# gameoflife.net
KiCad netlist of a schematic drawn in EAGLE
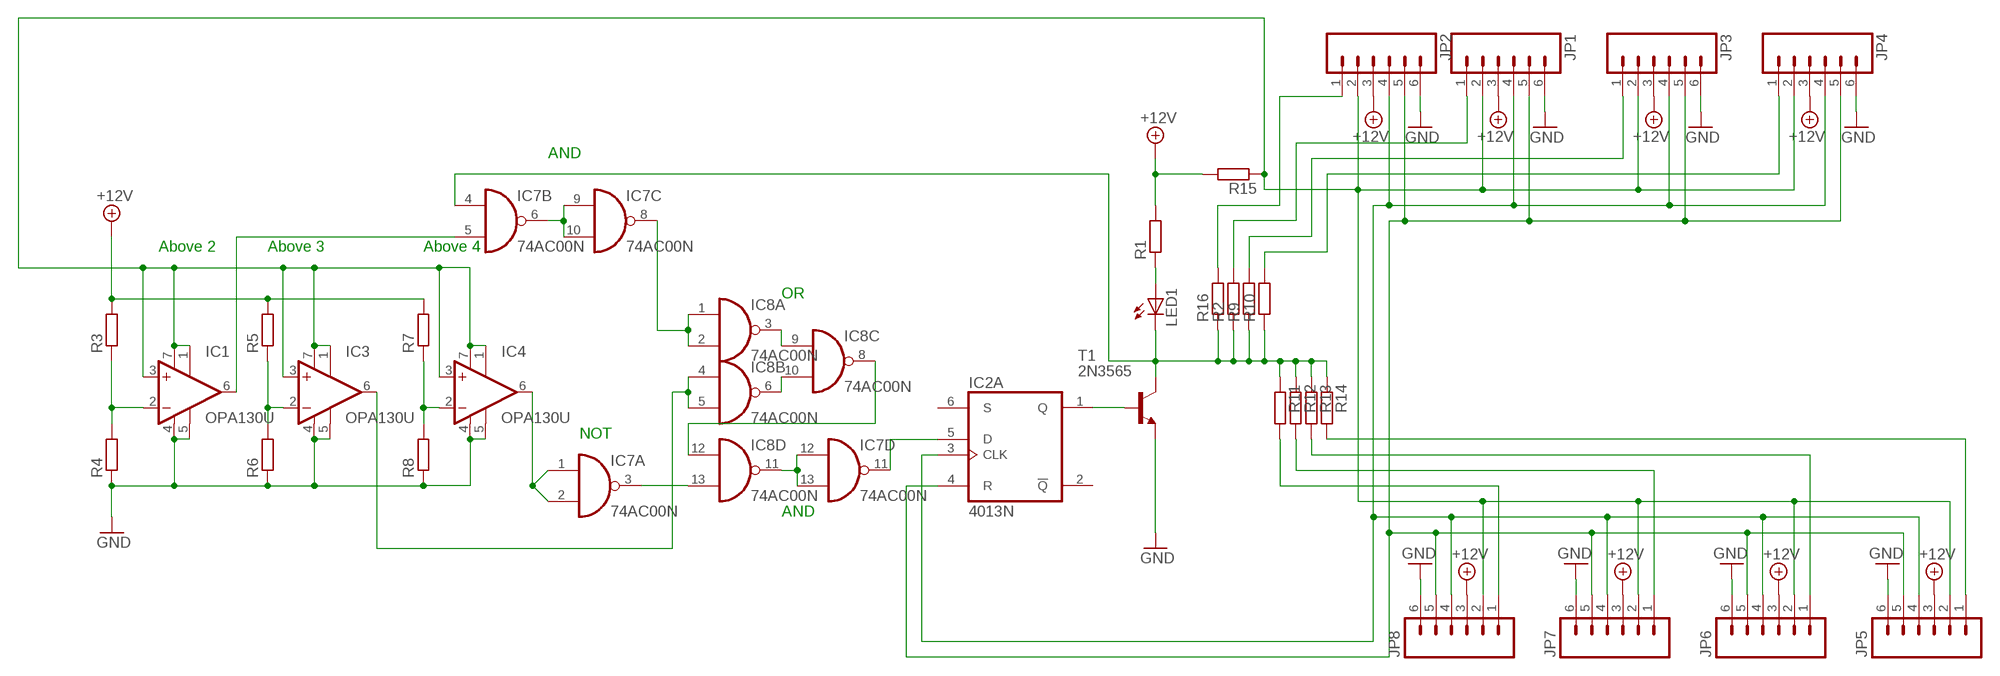
[diagram p0: schematic, sheet 1]

(export (version "E")
  (design (tool "Eeschema 10.0.6"))
  (components
    (comp (ref "IC1")
      (value "OPA130U")
      (footprint "eagle-import:SO08")
      (fields (field (name "MF") "TEXAS INSTRUMENTS") (field (name "MPN") "OPA130UA"))
      (libsource (lib "eagle-import") (part "OPA130U"))
    )
    (comp (ref "IC2")
      (value "4013N")
      (footprint "eagle-import:DIL14")
      (libsource (lib "eagle-import") (part "4013N"))
    )
    (comp (ref "IC3")
      (value "OPA130U")
      (footprint "eagle-import:SO08")
      (fields (field (name "MF") "TEXAS INSTRUMENTS") (field (name "MPN") "OPA130UA"))
      (libsource (lib "eagle-import") (part "OPA130U"))
    )
    (comp (ref "IC4")
      (value "OPA130U")
      (footprint "eagle-import:SO08")
      (fields (field (name "MF") "TEXAS INSTRUMENTS") (field (name "MPN") "OPA130UA"))
      (libsource (lib "eagle-import") (part "OPA130U"))
    )
    (comp (ref "IC7")
      (value "74AC00N")
      (footprint "eagle-import:DIL14")
      (libsource (lib "eagle-import") (part "7400NAC"))
    )
    (comp (ref "IC8")
      (value "74AC00N")
      (footprint "eagle-import:DIL14")
      (libsource (lib "eagle-import") (part "7400NAC"))
    )
    (comp (ref "JP1")
      (value "M06SILK_FEMALE_PTH")
      (footprint "eagle-import:1X06")
      (libsource (lib "eagle-import") (part "M06SILK_FEMALE_PTH"))
    )
    (comp (ref "JP2")
      (value "M06SILK_FEMALE_PTH")
      (footprint "eagle-import:1X06")
      (libsource (lib "eagle-import") (part "M06SILK_FEMALE_PTH"))
    )
    (comp (ref "JP3")
      (value "M06SILK_FEMALE_PTH")
      (footprint "eagle-import:1X06")
      (libsource (lib "eagle-import") (part "M06SILK_FEMALE_PTH"))
    )
    (comp (ref "JP4")
      (value "M06SILK_FEMALE_PTH")
      (footprint "eagle-import:1X06")
      (libsource (lib "eagle-import") (part "M06SILK_FEMALE_PTH"))
    )
    (comp (ref "JP5")
      (value "M06SILK_FEMALE_PTH")
      (footprint "eagle-import:1X06")
      (libsource (lib "eagle-import") (part "M06SILK_FEMALE_PTH"))
    )
    (comp (ref "JP6")
      (value "M06SILK_FEMALE_PTH")
      (footprint "eagle-import:1X06")
      (libsource (lib "eagle-import") (part "M06SILK_FEMALE_PTH"))
    )
    (comp (ref "JP7")
      (value "M06SILK_FEMALE_PTH")
      (footprint "eagle-import:1X06")
      (libsource (lib "eagle-import") (part "M06SILK_FEMALE_PTH"))
    )
    (comp (ref "JP8")
      (value "M06SILK_FEMALE_PTH")
      (footprint "eagle-import:1X06")
      (libsource (lib "eagle-import") (part "M06SILK_FEMALE_PTH"))
    )
    (comp (ref "LED1")
      (value "LED3MM")
      (footprint "eagle-import:LED3MM")
      (libsource (lib "eagle-import") (part "LED3MM"))
    )
    (comp (ref "R1")
      (value "R-EU_0207/10")
      (footprint "eagle-import:0207_10")
      (libsource (lib "eagle-import") (part "R-EU_0207/10"))
    )
    (comp (ref "R2")
      (value "R-EU_0207/10")
      (footprint "eagle-import:0207_10")
      (libsource (lib "eagle-import") (part "R-EU_0207/10"))
    )
    (comp (ref "R3")
      (value "R-EU_0207/10")
      (footprint "eagle-import:0207_10")
      (libsource (lib "eagle-import") (part "R-EU_0207/10"))
    )
    (comp (ref "R4")
      (value "R-EU_0207/10")
      (footprint "eagle-import:0207_10")
      (libsource (lib "eagle-import") (part "R-EU_0207/10"))
    )
    (comp (ref "R5")
      (value "R-EU_0207/10")
      (footprint "eagle-import:0207_10")
      (libsource (lib "eagle-import") (part "R-EU_0207/10"))
    )
    (comp (ref "R6")
      (value "R-EU_0207/10")
      (footprint "eagle-import:0207_10")
      (libsource (lib "eagle-import") (part "R-EU_0207/10"))
    )
    (comp (ref "R7")
      (value "R-EU_0207/10")
      (footprint "eagle-import:0207_10")
      (libsource (lib "eagle-import") (part "R-EU_0207/10"))
    )
    (comp (ref "R8")
      (value "R-EU_0207/10")
      (footprint "eagle-import:0207_10")
      (libsource (lib "eagle-import") (part "R-EU_0207/10"))
    )
    (comp (ref "R9")
      (value "R-EU_0207/10")
      (footprint "eagle-import:0207_10")
      (libsource (lib "eagle-import") (part "R-EU_0207/10"))
    )
    (comp (ref "R10")
      (value "R-EU_0207/10")
      (footprint "eagle-import:0207_10")
      (libsource (lib "eagle-import") (part "R-EU_0207/10"))
    )
    (comp (ref "R11")
      (value "R-EU_0207/10")
      (footprint "eagle-import:0207_10")
      (libsource (lib "eagle-import") (part "R-EU_0207/10"))
    )
    (comp (ref "R12")
      (value "R-EU_0207/10")
      (footprint "eagle-import:0207_10")
      (libsource (lib "eagle-import") (part "R-EU_0207/10"))
    )
    (comp (ref "R13")
      (value "R-EU_0207/10")
      (footprint "eagle-import:0207_10")
      (libsource (lib "eagle-import") (part "R-EU_0207/10"))
    )
    (comp (ref "R14")
      (value "R-EU_0207/10")
      (footprint "eagle-import:0207_10")
      (libsource (lib "eagle-import") (part "R-EU_0207/10"))
    )
    (comp (ref "R15")
      (value "R-EU_0207/10")
      (footprint "eagle-import:0207_10")
      (libsource (lib "eagle-import") (part "R-EU_0207/10"))
    )
    (comp (ref "R16")
      (value "R-EU_0207/10")
      (footprint "eagle-import:0207_10")
      (libsource (lib "eagle-import") (part "R-EU_0207/10"))
    )
    (comp (ref "T1")
      (value "2N3565")
      (footprint "eagle-import:TO92")
      (libsource (lib "eagle-import") (part "2N3565"))
    )
  )
  (nets
    (net (code "1") (name "+12V") (class "Default")
      (node (ref "JP1") (pin "3") (pinfunction "3_3") (pintype "passive"))
      (node (ref "JP2") (pin "3") (pinfunction "3_3") (pintype "passive"))
      (node (ref "JP3") (pin "3") (pinfunction "3_3") (pintype "passive"))
      (node (ref "JP4") (pin "3") (pinfunction "3_3") (pintype "passive"))
      (node (ref "JP5") (pin "3") (pinfunction "3_3") (pintype "passive"))
      (node (ref "JP6") (pin "3") (pinfunction "3_3") (pintype "passive"))
      (node (ref "JP7") (pin "3") (pinfunction "3_3") (pintype "passive"))
      (node (ref "JP8") (pin "3") (pinfunction "3_3") (pintype "passive"))
      (node (ref "R1") (pin "2") (pinfunction "2_2") (pintype "passive"))
      (node (ref "R15") (pin "2") (pinfunction "2_2") (pintype "passive"))
      (node (ref "R3") (pin "2") (pinfunction "2_2") (pintype "passive"))
      (node (ref "R5") (pin "2") (pinfunction "2_2") (pintype "passive"))
      (node (ref "R7") (pin "2") (pinfunction "2_2") (pintype "passive"))
    )
    (net (code "2") (name "GND") (class "Default")
      (node (ref "IC1") (pin "4") (pinfunction "V-_4") (pintype "power_in"))
      (node (ref "IC1") (pin "5") (pinfunction "TRIM2_5") (pintype "passive"))
      (node (ref "IC3") (pin "4") (pinfunction "V-_4") (pintype "power_in"))
      (node (ref "IC3") (pin "5") (pinfunction "TRIM2_5") (pintype "passive"))
      (node (ref "IC4") (pin "4") (pinfunction "V-_4") (pintype "power_in"))
      (node (ref "IC4") (pin "5") (pinfunction "TRIM2_5") (pintype "passive"))
      (node (ref "JP1") (pin "6") (pinfunction "6_6") (pintype "passive"))
      (node (ref "JP2") (pin "6") (pinfunction "6_6") (pintype "passive"))
      (node (ref "JP3") (pin "6") (pinfunction "6_6") (pintype "passive"))
      (node (ref "JP4") (pin "6") (pinfunction "6_6") (pintype "passive"))
      (node (ref "JP5") (pin "6") (pinfunction "6_6") (pintype "passive"))
      (node (ref "JP6") (pin "6") (pinfunction "6_6") (pintype "passive"))
      (node (ref "JP7") (pin "6") (pinfunction "6_6") (pintype "passive"))
      (node (ref "JP8") (pin "6") (pinfunction "6_6") (pintype "passive"))
      (node (ref "R4") (pin "1") (pinfunction "1_1") (pintype "passive"))
      (node (ref "R6") (pin "1") (pinfunction "1_1") (pintype "passive"))
      (node (ref "R8") (pin "1") (pinfunction "1_1") (pintype "passive"))
      (node (ref "T1") (pin "3") (pinfunction "E_3") (pintype "passive"))
    )
    (net (code "3") (name "Net-(IC1-+IN)") (class "Default")
      (node (ref "IC1") (pin "1") (pinfunction "TRIM1_1") (pintype "passive"))
      (node (ref "IC1") (pin "3") (pinfunction "+IN_3") (pintype "input"))
      (node (ref "IC1") (pin "7") (pinfunction "V+_7") (pintype "power_in"))
      (node (ref "IC3") (pin "1") (pinfunction "TRIM1_1") (pintype "passive"))
      (node (ref "IC3") (pin "3") (pinfunction "+IN_3") (pintype "input"))
      (node (ref "IC3") (pin "7") (pinfunction "V+_7") (pintype "power_in"))
      (node (ref "IC4") (pin "1") (pinfunction "TRIM1_1") (pintype "passive"))
      (node (ref "IC4") (pin "3") (pinfunction "+IN_3") (pintype "input"))
      (node (ref "IC4") (pin "7") (pinfunction "V+_7") (pintype "power_in"))
      (node (ref "JP1") (pin "2") (pinfunction "2_2") (pintype "passive"))
      (node (ref "JP2") (pin "2") (pinfunction "2_2") (pintype "passive"))
      (node (ref "JP3") (pin "2") (pinfunction "2_2") (pintype "passive"))
      (node (ref "JP4") (pin "2") (pinfunction "2_2") (pintype "passive"))
      (node (ref "JP5") (pin "2") (pinfunction "2_2") (pintype "passive"))
      (node (ref "JP6") (pin "2") (pinfunction "2_2") (pintype "passive"))
      (node (ref "JP7") (pin "2") (pinfunction "2_2") (pintype "passive"))
      (node (ref "JP8") (pin "2") (pinfunction "2_2") (pintype "passive"))
      (node (ref "R15") (pin "1") (pinfunction "1_1") (pintype "passive"))
    )
    (net (code "4") (name "Net-(IC1--IN)") (class "Default")
      (node (ref "IC1") (pin "2") (pinfunction "-IN_2") (pintype "input"))
      (node (ref "R3") (pin "1") (pinfunction "1_1") (pintype "passive"))
      (node (ref "R4") (pin "2") (pinfunction "2_2") (pintype "passive"))
    )
    (net (code "5") (name "Net-(IC1-OUT)") (class "Default")
      (node (ref "IC1") (pin "6") (pinfunction "OUT_6") (pintype "output"))
      (node (ref "IC7") (pin "5") (pinfunction "I1_5") (pintype "input"))
    )
    (net (code "6") (name "Net-(IC2A-CLK)") (class "Default")
      (node (ref "IC2") (pin "3") (pinfunction "CLK_3") (pintype "input"))
      (node (ref "JP1") (pin "4") (pinfunction "4_4") (pintype "passive"))
      (node (ref "JP2") (pin "4") (pinfunction "4_4") (pintype "passive"))
      (node (ref "JP3") (pin "4") (pinfunction "4_4") (pintype "passive"))
      (node (ref "JP4") (pin "4") (pinfunction "4_4") (pintype "passive"))
      (node (ref "JP5") (pin "4") (pinfunction "4_4") (pintype "passive"))
      (node (ref "JP6") (pin "4") (pinfunction "4_4") (pintype "passive"))
      (node (ref "JP7") (pin "4") (pinfunction "4_4") (pintype "passive"))
      (node (ref "JP8") (pin "4") (pinfunction "4_4") (pintype "passive"))
    )
    (net (code "7") (name "Net-(IC2A-D)") (class "Default")
      (node (ref "IC2") (pin "5") (pinfunction "D_5") (pintype "input"))
      (node (ref "IC7") (pin "11") (pinfunction "O_11") (pintype "output"))
    )
    (net (code "8") (name "Net-(IC2A-Q)") (class "Default")
      (node (ref "IC2") (pin "1") (pinfunction "Q_1") (pintype "output"))
      (node (ref "T1") (pin "2") (pinfunction "B_2") (pintype "passive"))
    )
    (net (code "9") (name "Net-(IC2A-R)") (class "Default")
      (node (ref "IC2") (pin "4") (pinfunction "R_4") (pintype "input"))
      (node (ref "JP1") (pin "5") (pinfunction "5_5") (pintype "passive"))
      (node (ref "JP2") (pin "5") (pinfunction "5_5") (pintype "passive"))
      (node (ref "JP3") (pin "5") (pinfunction "5_5") (pintype "passive"))
      (node (ref "JP4") (pin "5") (pinfunction "5_5") (pintype "passive"))
      (node (ref "JP5") (pin "5") (pinfunction "5_5") (pintype "passive"))
      (node (ref "JP6") (pin "5") (pinfunction "5_5") (pintype "passive"))
      (node (ref "JP7") (pin "5") (pinfunction "5_5") (pintype "passive"))
      (node (ref "JP8") (pin "5") (pinfunction "5_5") (pintype "passive"))
    )
    (net (code "10") (name "Net-(IC3--IN)") (class "Default")
      (node (ref "IC3") (pin "2") (pinfunction "-IN_2") (pintype "input"))
      (node (ref "R5") (pin "1") (pinfunction "1_1") (pintype "passive"))
      (node (ref "R6") (pin "2") (pinfunction "2_2") (pintype "passive"))
    )
    (net (code "11") (name "Net-(IC3-OUT)") (class "Default")
      (node (ref "IC3") (pin "6") (pinfunction "OUT_6") (pintype "output"))
      (node (ref "IC8") (pin "4") (pinfunction "I0_4") (pintype "input"))
      (node (ref "IC8") (pin "5") (pinfunction "I1_5") (pintype "input"))
    )
    (net (code "12") (name "Net-(IC4--IN)") (class "Default")
      (node (ref "IC4") (pin "2") (pinfunction "-IN_2") (pintype "input"))
      (node (ref "R7") (pin "1") (pinfunction "1_1") (pintype "passive"))
      (node (ref "R8") (pin "2") (pinfunction "2_2") (pintype "passive"))
    )
    (net (code "13") (name "Net-(IC4-OUT)") (class "Default")
      (node (ref "IC4") (pin "6") (pinfunction "OUT_6") (pintype "output"))
      (node (ref "IC7") (pin "1") (pinfunction "I0_1") (pintype "input"))
      (node (ref "IC7") (pin "2") (pinfunction "I1_2") (pintype "input"))
    )
    (net (code "14") (name "Net-(IC7A-O)") (class "Default")
      (node (ref "IC7") (pin "3") (pinfunction "O_3") (pintype "output"))
      (node (ref "IC8") (pin "13") (pinfunction "I1_13") (pintype "input"))
    )
    (net (code "15") (name "Net-(IC7B-I0)") (class "Default")
      (node (ref "IC7") (pin "4") (pinfunction "I0_4") (pintype "input"))
      (node (ref "LED1") (pin "K") (pinfunction "C_K") (pintype "passive"))
      (node (ref "R10") (pin "1") (pinfunction "1_1") (pintype "passive"))
      (node (ref "R11") (pin "1") (pinfunction "1_1") (pintype "passive"))
      (node (ref "R12") (pin "1") (pinfunction "1_1") (pintype "passive"))
      (node (ref "R13") (pin "1") (pinfunction "1_1") (pintype "passive"))
      (node (ref "R14") (pin "1") (pinfunction "1_1") (pintype "passive"))
      (node (ref "R16") (pin "1") (pinfunction "1_1") (pintype "passive"))
      (node (ref "R2") (pin "1") (pinfunction "1_1") (pintype "passive"))
      (node (ref "R9") (pin "1") (pinfunction "1_1") (pintype "passive"))
      (node (ref "T1") (pin "1") (pinfunction "C_1") (pintype "passive"))
    )
    (net (code "16") (name "Net-(IC7B-O)") (class "Default")
      (node (ref "IC7") (pin "10") (pinfunction "I1_10") (pintype "input"))
      (node (ref "IC7") (pin "6") (pinfunction "O_6") (pintype "output"))
      (node (ref "IC7") (pin "9") (pinfunction "I0_9") (pintype "input"))
    )
    (net (code "17") (name "Net-(IC7C-O)") (class "Default")
      (node (ref "IC7") (pin "8") (pinfunction "O_8") (pintype "output"))
      (node (ref "IC8") (pin "1") (pinfunction "I0_1") (pintype "input"))
      (node (ref "IC8") (pin "2") (pinfunction "I1_2") (pintype "input"))
    )
    (net (code "18") (name "Net-(IC7D-I0)") (class "Default")
      (node (ref "IC7") (pin "12") (pinfunction "I0_12") (pintype "input"))
      (node (ref "IC7") (pin "13") (pinfunction "I1_13") (pintype "input"))
      (node (ref "IC8") (pin "11") (pinfunction "O_11") (pintype "output"))
    )
    (net (code "19") (name "Net-(IC8A-O)") (class "Default")
      (node (ref "IC8") (pin "3") (pinfunction "O_3") (pintype "output"))
      (node (ref "IC8") (pin "9") (pinfunction "I0_9") (pintype "input"))
    )
    (net (code "20") (name "Net-(IC8B-O)") (class "Default")
      (node (ref "IC8") (pin "10") (pinfunction "I1_10") (pintype "input"))
      (node (ref "IC8") (pin "6") (pinfunction "O_6") (pintype "output"))
    )
    (net (code "21") (name "Net-(IC8C-O)") (class "Default")
      (node (ref "IC8") (pin "12") (pinfunction "I0_12") (pintype "input"))
      (node (ref "IC8") (pin "8") (pinfunction "O_8") (pintype "output"))
    )
    (net (code "22") (name "Net-(JP1-Pad1)") (class "Default")
      (node (ref "JP1") (pin "1") (pinfunction "1_1") (pintype "passive"))
      (node (ref "R2") (pin "2") (pinfunction "2_2") (pintype "passive"))
    )
    (net (code "23") (name "Net-(JP2-Pad1)") (class "Default")
      (node (ref "JP2") (pin "1") (pinfunction "1_1") (pintype "passive"))
      (node (ref "R16") (pin "2") (pinfunction "2_2") (pintype "passive"))
    )
    (net (code "24") (name "Net-(JP3-Pad1)") (class "Default")
      (node (ref "JP3") (pin "1") (pinfunction "1_1") (pintype "passive"))
      (node (ref "R9") (pin "2") (pinfunction "2_2") (pintype "passive"))
    )
    (net (code "25") (name "Net-(JP4-Pad1)") (class "Default")
      (node (ref "JP4") (pin "1") (pinfunction "1_1") (pintype "passive"))
      (node (ref "R10") (pin "2") (pinfunction "2_2") (pintype "passive"))
    )
    (net (code "26") (name "Net-(JP5-Pad1)") (class "Default")
      (node (ref "JP5") (pin "1") (pinfunction "1_1") (pintype "passive"))
      (node (ref "R14") (pin "2") (pinfunction "2_2") (pintype "passive"))
    )
    (net (code "27") (name "Net-(JP6-Pad1)") (class "Default")
      (node (ref "JP6") (pin "1") (pinfunction "1_1") (pintype "passive"))
      (node (ref "R13") (pin "2") (pinfunction "2_2") (pintype "passive"))
    )
    (net (code "28") (name "Net-(JP7-Pad1)") (class "Default")
      (node (ref "JP7") (pin "1") (pinfunction "1_1") (pintype "passive"))
      (node (ref "R12") (pin "2") (pinfunction "2_2") (pintype "passive"))
    )
    (net (code "29") (name "Net-(JP8-Pad1)") (class "Default")
      (node (ref "JP8") (pin "1") (pinfunction "1_1") (pintype "passive"))
      (node (ref "R11") (pin "2") (pinfunction "2_2") (pintype "passive"))
    )
    (net (code "30") (name "Net-(LED1-PadA)") (class "Default")
      (node (ref "LED1") (pin "A") (pinfunction "A_A") (pintype "passive"))
      (node (ref "R1") (pin "1") (pinfunction "1_1") (pintype "passive"))
    )
    (net (code "31") (name "unconnected-(IC2A-S-Pad6)") (class "Default")
      (node (ref "IC2") (pin "6") (pinfunction "S_6") (pintype "input"))
    )
    (net (code "32") (name "unconnected-(IC2A-~{Q}-Pad2)") (class "Default")
      (node (ref "IC2") (pin "2") (pinfunction "~{Q}_2") (pintype "output"))
    )
  )
)
